# Arduino-Rework_Station.net
KiCad netlist of a schematic drawn in EAGLE
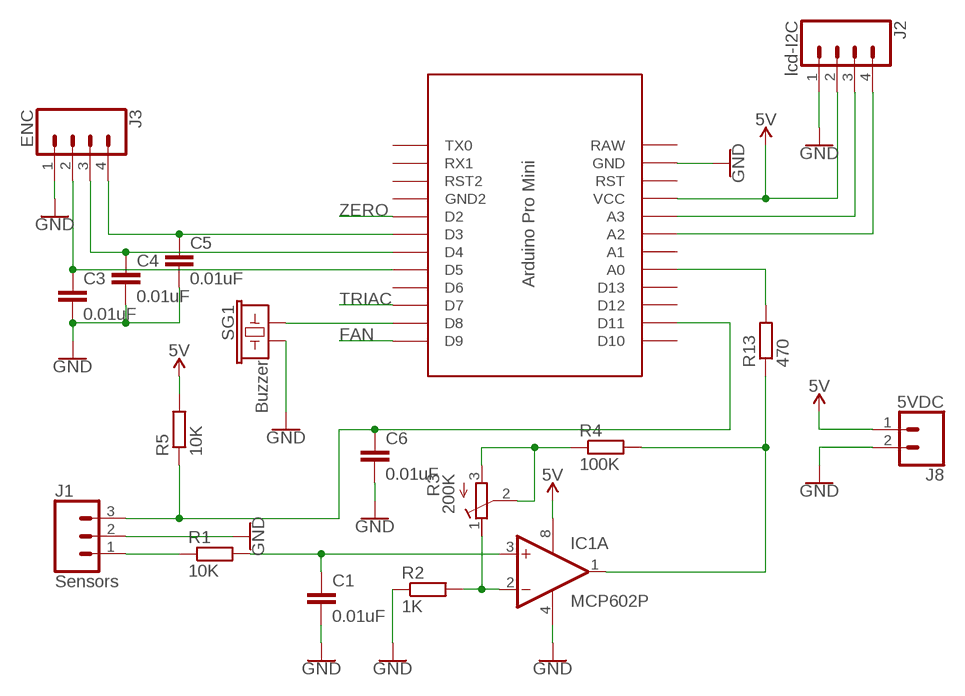
[diagram p0: schematic, sheet 1]
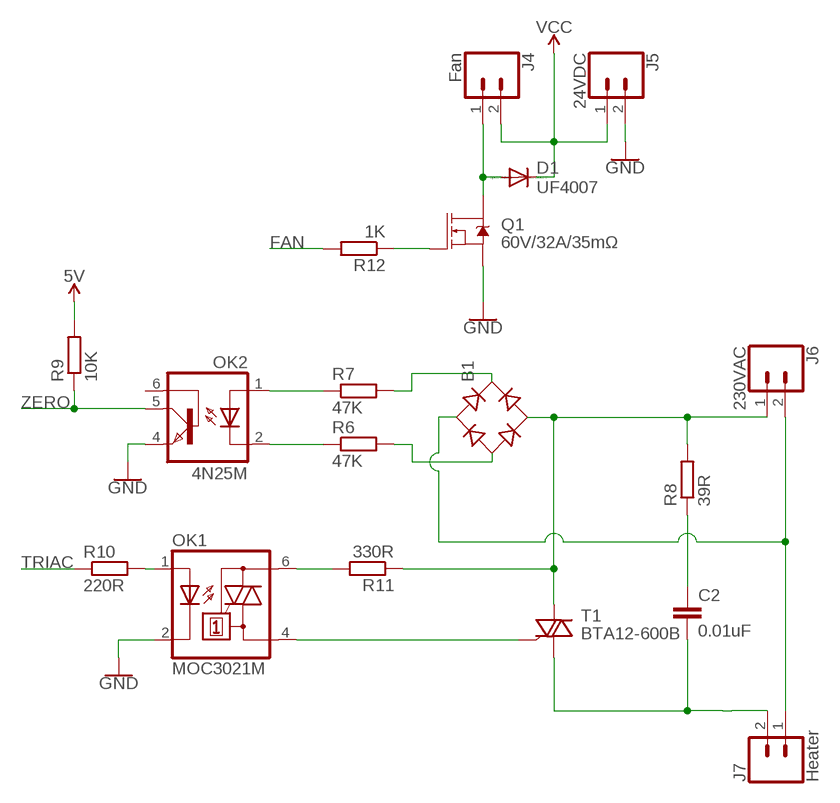
[diagram p1: schematic, sheet 2]

(export (version "E")
  (design (tool "Eeschema 10.0.6"))
  (components
    (comp (ref "C1")
      (value "0.01uF")
      (footprint "eagle-import:C025-024X044")
      (libsource (lib "eagle-import") (part "C-EU025-024X044"))
    )
    (comp (ref "C3")
      (value "0.01uF")
      (footprint "eagle-import:C025-024X044")
      (libsource (lib "eagle-import") (part "C-EU025-024X044"))
    )
    (comp (ref "C4")
      (value "0.01uF")
      (footprint "eagle-import:C025-024X044")
      (libsource (lib "eagle-import") (part "C-EU025-024X044"))
    )
    (comp (ref "C5")
      (value "0.01uF")
      (footprint "eagle-import:C025-024X044")
      (libsource (lib "eagle-import") (part "C-EU025-024X044"))
    )
    (comp (ref "C6")
      (value "0.01uF")
      (footprint "eagle-import:C025-024X044")
      (libsource (lib "eagle-import") (part "C-EU025-024X044"))
    )
    (comp (ref "IC1")
      (value "MCP602P")
      (footprint "eagle-import:DIL08")
      (libsource (lib "eagle-import") (part "MCP602P"))
    )
    (comp (ref "J1")
      (value "Sensors")
      (footprint "eagle-import:MOLEX-1X3")
      (libsource (lib "eagle-import") (part "CONN_03POLAR"))
    )
    (comp (ref "J2")
      (value "lcd-I2C")
      (footprint "eagle-import:MOLEX-1X4")
      (libsource (lib "eagle-import") (part "CONN_04POLAR"))
    )
    (comp (ref "J3")
      (value "ENC")
      (footprint "eagle-import:MOLEX-1X4")
      (libsource (lib "eagle-import") (part "CONN_04POLAR"))
    )
    (comp (ref "J8")
      (value "5VDC")
      (footprint "eagle-import:MOLEX-1X2")
      (libsource (lib "eagle-import") (part "CONN_02POLAR"))
    )
    (comp (ref "R1")
      (value "10K")
      (footprint "eagle-import:0207_10")
      (libsource (lib "eagle-import") (part "R-EU_0207/10"))
    )
    (comp (ref "R2")
      (value "1K")
      (footprint "eagle-import:0207_10")
      (libsource (lib "eagle-import") (part "R-EU_0207/10"))
    )
    (comp (ref "R3")
      (value "200K")
      (footprint "eagle-import:RTRIM3006P")
      (libsource (lib "eagle-import") (part "R-TRIMM3006P"))
    )
    (comp (ref "R4")
      (value "100K")
      (footprint "eagle-import:0207_10")
      (libsource (lib "eagle-import") (part "R-EU_0207/10"))
    )
    (comp (ref "R5")
      (value "10K")
      (footprint "eagle-import:0207_10")
      (libsource (lib "eagle-import") (part "R-EU_0207/10"))
    )
    (comp (ref "R13")
      (value "470")
      (footprint "eagle-import:0207_10")
      (libsource (lib "eagle-import") (part "R-EU_0207/10"))
    )
    (comp (ref "SG1")
      (value "Buzzer")
      (footprint "eagle-import:BUZZER-12MM")
      (libsource (lib "eagle-import") (part "BUZZER-PTH"))
    )
    (comp (ref "U$1")
      (value "PRO-MINI")
      (footprint "eagle-import:PRO-MINI")
      (libsource (lib "eagle-import") (part "PRO-MINI"))
    )
    (comp (ref "B1")
      (value "RB1A")
      (footprint "eagle-import:RB1A")
      (libsource (lib "eagle-import") (part "RB1A"))
    )
    (comp (ref "C2")
      (value "0.01uF")
      (footprint "eagle-import:C050-045X075")
      (libsource (lib "eagle-import") (part "C-EU050-045X075"))
    )
    (comp (ref "D1")
      (value "UF4007")
      (footprint "eagle-import:DO41-10")
      (libsource (lib "eagle-import") (part "1N4004"))
    )
    (comp (ref "J4")
      (value "Fan")
      (footprint "eagle-import:MOLEX-1X2")
      (libsource (lib "eagle-import") (part "CONN_02POLAR"))
    )
    (comp (ref "J5")
      (value "24VDC")
      (footprint "eagle-import:SCREWTERMINAL-5MM-2")
      (libsource (lib "eagle-import") (part "CONN_025MM"))
    )
    (comp (ref "J6")
      (value "230VAC")
      (footprint "eagle-import:1X02_XTRA_BIG")
      (libsource (lib "eagle-import") (part "CONN_02PTH4"))
    )
    (comp (ref "J7")
      (value "Heater")
      (footprint "eagle-import:1X02_XTRA_BIG")
      (libsource (lib "eagle-import") (part "CONN_02PTH4"))
    )
    (comp (ref "OK1")
      (value "MOC3021M")
      (footprint "eagle-import:DIL06")
      (fields (field (name "MF") "FAIRCHILD SEMICONDUCTOR") (field (name "MPN") "MOC3021-M"))
      (libsource (lib "eagle-import") (part "MOC30M21"))
    )
    (comp (ref "OK2")
      (value "4N25M")
      (footprint "eagle-import:DIL06")
      (fields (field (name "MPN") "4N25-M"))
      (libsource (lib "eagle-import") (part "4N?M25"))
    )
    (comp (ref "Q1")
      (value "60V/32A/35mΩ")
      (footprint "eagle-import:TO220V")
      (libsource (lib "eagle-import") (part "MOSFET-NCH-FQP30N06L"))
    )
    (comp (ref "R6")
      (value "47K")
      (footprint "eagle-import:0204_7")
      (libsource (lib "eagle-import") (part "R-EU_0204/7"))
    )
    (comp (ref "R7")
      (value "47K")
      (footprint "eagle-import:0204_7")
      (libsource (lib "eagle-import") (part "R-EU_0204/7"))
    )
    (comp (ref "R8")
      (value "39R")
      (footprint "eagle-import:0617_22")
      (libsource (lib "eagle-import") (part "R-EU_0617/22"))
    )
    (comp (ref "R9")
      (value "10K")
      (footprint "eagle-import:0204_7")
      (libsource (lib "eagle-import") (part "R-EU_0204/7"))
    )
    (comp (ref "R10")
      (value "220R")
      (footprint "eagle-import:0204_7")
      (libsource (lib "eagle-import") (part "R-EU_0204/7"))
    )
    (comp (ref "R11")
      (value "330R")
      (footprint "eagle-import:0204_7")
      (libsource (lib "eagle-import") (part "R-EU_0204/7"))
    )
    (comp (ref "R12")
      (value "1K")
      (footprint "eagle-import:0204_7")
      (libsource (lib "eagle-import") (part "R-EU_0204/7"))
    )
    (comp (ref "T1")
      (value "BTA12-600B")
      (footprint "eagle-import:TO220BV")
      (libsource (lib "eagle-import") (part "BT138-V"))
    )
  )
  (nets
    (net (code "1") (name "5V") (class "Default")
      (node (ref "IC1") (pin "8") (pinfunction "V+_8") (pintype "power_in"))
      (node (ref "J2") (pin "2") (pinfunction "2_2") (pintype "passive"))
      (node (ref "J8") (pin "1") (pinfunction "1_1") (pintype "passive"))
      (node (ref "R5") (pin "2") (pinfunction "2_2") (pintype "passive"))
      (node (ref "R9") (pin "2") (pinfunction "2_2") (pintype "passive"))
      (node (ref "U$1") (pin "VCC") (pinfunction "VCC_VCC") (pintype "bidirectional"))
    )
    (net (code "2") (name "FAN") (class "Default")
      (node (ref "R12") (pin "2") (pinfunction "2_2") (pintype "passive"))
      (node (ref "U$1") (pin "D9") (pinfunction "D9_D9") (pintype "bidirectional"))
    )
    (net (code "3") (name "GND") (class "Default")
      (node (ref "C1") (pin "2") (pinfunction "2_2") (pintype "passive"))
      (node (ref "C3") (pin "2") (pinfunction "2_2") (pintype "passive"))
      (node (ref "C4") (pin "2") (pinfunction "2_2") (pintype "passive"))
      (node (ref "C5") (pin "2") (pinfunction "2_2") (pintype "passive"))
      (node (ref "C6") (pin "2") (pinfunction "2_2") (pintype "passive"))
      (node (ref "IC1") (pin "4") (pinfunction "V-_4") (pintype "power_in"))
      (node (ref "J1") (pin "2") (pinfunction "2_2") (pintype "passive"))
      (node (ref "J2") (pin "1") (pinfunction "1_1") (pintype "passive"))
      (node (ref "J3") (pin "1") (pinfunction "1_1") (pintype "passive"))
      (node (ref "J5") (pin "2") (pinfunction "2_2") (pintype "passive"))
      (node (ref "J8") (pin "2") (pinfunction "2_2") (pintype "passive"))
      (node (ref "OK1") (pin "2") (pinfunction "C_2") (pintype "passive"))
      (node (ref "OK2") (pin "4") (pinfunction "EMI_4") (pintype "passive"))
      (node (ref "Q1") (pin "3") (pinfunction "S_3") (pintype "bidirectional"))
      (node (ref "R2") (pin "1") (pinfunction "1_1") (pintype "passive"))
      (node (ref "SG1") (pin "-") (pinfunction "2_-") (pintype "passive"))
      (node (ref "U$1") (pin "GND") (pinfunction "GND_GND") (pintype "input"))
    )
    (net (code "4") (name "Net-(B1-Pad+)") (class "Default")
      (node (ref "B1") (pin "+") (pinfunction "+_+") (pintype "passive"))
      (node (ref "R7") (pin "2") (pinfunction "2_2") (pintype "passive"))
    )
    (net (code "5") (name "Net-(B1-Pad-)") (class "Default")
      (node (ref "B1") (pin "-") (pinfunction "-_-") (pintype "passive"))
      (node (ref "R6") (pin "2") (pinfunction "2_2") (pintype "passive"))
    )
    (net (code "6") (name "Net-(B1-PadAC1)") (class "Default")
      (node (ref "B1") (pin "AC1") (pinfunction "AC1_AC1") (pintype "passive"))
      (node (ref "J6") (pin "2") (pinfunction "2_2") (pintype "passive"))
      (node (ref "J7") (pin "1") (pinfunction "1_1") (pintype "passive"))
    )
    (net (code "7") (name "Net-(C2-Pad1)") (class "Default")
      (node (ref "C2") (pin "1") (pinfunction "1_1") (pintype "passive"))
      (node (ref "R8") (pin "1") (pinfunction "1_1") (pintype "passive"))
    )
    (net (code "8") (name "Net-(C3-Pad1)") (class "Default")
      (node (ref "C3") (pin "1") (pinfunction "1_1") (pintype "passive"))
      (node (ref "J3") (pin "2") (pinfunction "2_2") (pintype "passive"))
      (node (ref "U$1") (pin "D5") (pinfunction "D5_D5") (pintype "bidirectional"))
    )
    (net (code "9") (name "Net-(C4-Pad1)") (class "Default")
      (node (ref "C4") (pin "1") (pinfunction "1_1") (pintype "passive"))
      (node (ref "J3") (pin "3") (pinfunction "3_3") (pintype "passive"))
      (node (ref "U$1") (pin "D4") (pinfunction "D4_D4") (pintype "bidirectional"))
    )
    (net (code "10") (name "Net-(C5-Pad1)") (class "Default")
      (node (ref "C5") (pin "1") (pinfunction "1_1") (pintype "passive"))
      (node (ref "J3") (pin "4") (pinfunction "4_4") (pintype "passive"))
      (node (ref "U$1") (pin "D3") (pinfunction "D3_D3") (pintype "bidirectional"))
    )
    (net (code "11") (name "Net-(C6-Pad1)") (class "Default")
      (node (ref "C6") (pin "1") (pinfunction "1_1") (pintype "passive"))
      (node (ref "J1") (pin "3") (pinfunction "3_3") (pintype "passive"))
      (node (ref "R5") (pin "1") (pinfunction "1_1") (pintype "passive"))
      (node (ref "U$1") (pin "D11") (pinfunction "D11_D11") (pintype "bidirectional"))
    )
    (net (code "12") (name "Net-(IC1A-+IN)") (class "Default")
      (node (ref "C1") (pin "1") (pinfunction "1_1") (pintype "passive"))
      (node (ref "IC1") (pin "3") (pinfunction "+IN_3") (pintype "input"))
      (node (ref "R1") (pin "2") (pinfunction "2_2") (pintype "passive"))
    )
    (net (code "13") (name "Net-(IC1A--IN)") (class "Default")
      (node (ref "IC1") (pin "2") (pinfunction "-IN_2") (pintype "input"))
      (node (ref "R2") (pin "2") (pinfunction "2_2") (pintype "passive"))
      (node (ref "R3") (pin "1") (pinfunction "E_1") (pintype "passive"))
    )
    (net (code "14") (name "Net-(IC1A-OUT)") (class "Default")
      (node (ref "IC1") (pin "1") (pinfunction "OUT_1") (pintype "output"))
      (node (ref "R13") (pin "1") (pinfunction "1_1") (pintype "passive"))
      (node (ref "R4") (pin "2") (pinfunction "2_2") (pintype "passive"))
    )
    (net (code "15") (name "Net-(J1-Pad1)") (class "Default")
      (node (ref "J1") (pin "1") (pinfunction "1_1") (pintype "passive"))
      (node (ref "R1") (pin "1") (pinfunction "1_1") (pintype "passive"))
    )
    (net (code "16") (name "Net-(J2-Pad3)") (class "Default")
      (node (ref "J2") (pin "3") (pinfunction "3_3") (pintype "passive"))
      (node (ref "U$1") (pin "A3") (pinfunction "A3_A3") (pintype "bidirectional"))
    )
    (net (code "17") (name "Net-(J2-Pad4)") (class "Default")
      (node (ref "J2") (pin "4") (pinfunction "4_4") (pintype "passive"))
      (node (ref "U$1") (pin "A2") (pinfunction "A2_A2") (pintype "bidirectional"))
    )
    (net (code "18") (name "Net-(OK1-A)") (class "Default")
      (node (ref "OK1") (pin "1") (pinfunction "A_1") (pintype "passive"))
      (node (ref "R10") (pin "2") (pinfunction "2_2") (pintype "passive"))
    )
    (net (code "19") (name "Net-(OK1-A1)") (class "Default")
      (node (ref "OK1") (pin "4") (pinfunction "A1_4") (pintype "passive"))
      (node (ref "T1") (pin "G") (pinfunction "G_G") (pintype "passive"))
    )
    (net (code "20") (name "Net-(OK1-A2)") (class "Default")
      (node (ref "OK1") (pin "6") (pinfunction "A2_6") (pintype "passive"))
      (node (ref "R11") (pin "2") (pinfunction "2_2") (pintype "passive"))
    )
    (net (code "21") (name "Net-(OK2-A)") (class "Default")
      (node (ref "OK2") (pin "1") (pinfunction "A_1") (pintype "passive"))
      (node (ref "R7") (pin "1") (pinfunction "1_1") (pintype "passive"))
    )
    (net (code "22") (name "Net-(OK2-C)") (class "Default")
      (node (ref "OK2") (pin "2") (pinfunction "C_2") (pintype "passive"))
      (node (ref "R6") (pin "1") (pinfunction "1_1") (pintype "passive"))
    )
    (net (code "23") (name "Net-(Q1-D)") (class "Default")
      (node (ref "D1") (pin "A") (pinfunction "A_A") (pintype "passive"))
      (node (ref "J4") (pin "1") (pinfunction "1_1") (pintype "passive"))
      (node (ref "Q1") (pin "2") (pinfunction "D_2") (pintype "bidirectional"))
    )
    (net (code "24") (name "Net-(Q1-G)") (class "Default")
      (node (ref "Q1") (pin "1") (pinfunction "G_1") (pintype "bidirectional"))
      (node (ref "R12") (pin "1") (pinfunction "1_1") (pintype "passive"))
    )
    (net (code "25") (name "Net-(R3-A)") (class "Default")
      (node (ref "R3") (pin "2") (pinfunction "S_2") (pintype "passive"))
      (node (ref "R3") (pin "3") (pinfunction "A_3") (pintype "passive"))
      (node (ref "R4") (pin "1") (pinfunction "1_1") (pintype "passive"))
    )
    (net (code "26") (name "Net-(R13-Pad2)") (class "Default")
      (node (ref "R13") (pin "2") (pinfunction "2_2") (pintype "passive"))
      (node (ref "U$1") (pin "A0") (pinfunction "A0_A0") (pintype "bidirectional"))
    )
    (net (code "27") (name "Net-(SG1-1)") (class "Default")
      (node (ref "SG1") (pin "+") (pinfunction "1_+") (pintype "passive"))
      (node (ref "U$1") (pin "D8") (pinfunction "D8_D8") (pintype "bidirectional"))
    )
    (net (code "28") (name "Net-(T1-A1)") (class "Default")
      (node (ref "C2") (pin "2") (pinfunction "2_2") (pintype "passive"))
      (node (ref "J7") (pin "2") (pinfunction "2_2") (pintype "passive"))
      (node (ref "T1") (pin "T1") (pinfunction "A1_T1") (pintype "passive"))
    )
    (net (code "29") (name "Net-(T1-A2)") (class "Default")
      (node (ref "B1") (pin "AC2") (pinfunction "AC2_AC2") (pintype "passive"))
      (node (ref "J6") (pin "1") (pinfunction "1_1") (pintype "passive"))
      (node (ref "R11") (pin "1") (pinfunction "1_1") (pintype "passive"))
      (node (ref "R8") (pin "2") (pinfunction "2_2") (pintype "passive"))
      (node (ref "T1") (pin "T2") (pinfunction "A2_T2") (pintype "passive"))
    )
    (net (code "30") (name "RAW") (class "Default")
      (node (ref "U$1") (pin "RAW") (pinfunction "RAW_RAW") (pintype "power_in"))
    )
    (net (code "31") (name "TRIAC") (class "Default")
      (node (ref "R10") (pin "1") (pinfunction "1_1") (pintype "passive"))
      (node (ref "U$1") (pin "D7") (pinfunction "D7_D7") (pintype "bidirectional"))
    )
    (net (code "32") (name "VCC") (class "Default")
      (node (ref "D1") (pin "C") (pinfunction "C_C") (pintype "passive"))
      (node (ref "J4") (pin "2") (pinfunction "2_2") (pintype "passive"))
      (node (ref "J5") (pin "1") (pinfunction "1_1") (pintype "passive"))
    )
    (net (code "33") (name "ZERO") (class "Default")
      (node (ref "OK2") (pin "5") (pinfunction "COL_5") (pintype "passive"))
      (node (ref "R9") (pin "1") (pinfunction "1_1") (pintype "passive"))
      (node (ref "U$1") (pin "D2") (pinfunction "D2_D2") (pintype "bidirectional"))
    )
    (net (code "34") (name "unconnected-(OK2-BAS-Pad6)") (class "Default")
      (node (ref "OK2") (pin "6") (pinfunction "BAS_6") (pintype "passive"))
    )
    (net (code "35") (name "unconnected-(U$1-GND2-PadGND1)") (class "Default")
      (node (ref "U$1") (pin "GND1") (pinfunction "GND2_GND1") (pintype "bidirectional"))
    )
    (net (code "36") (name "unconnected-(U$1-PadA1)") (class "Default")
      (node (ref "U$1") (pin "A1") (pinfunction "A1_A1") (pintype "bidirectional"))
    )
    (net (code "37") (name "unconnected-(U$1-PadD6)") (class "Default")
      (node (ref "U$1") (pin "D6") (pinfunction "D6_D6") (pintype "bidirectional"))
    )
    (net (code "38") (name "unconnected-(U$1-PadD10)") (class "Default")
      (node (ref "U$1") (pin "D10") (pinfunction "D10_D10") (pintype "bidirectional"))
    )
    (net (code "39") (name "unconnected-(U$1-PadD12)") (class "Default")
      (node (ref "U$1") (pin "D12") (pinfunction "D12_D12") (pintype "bidirectional"))
    )
    (net (code "40") (name "unconnected-(U$1-PadD13)") (class "Default")
      (node (ref "U$1") (pin "D13") (pinfunction "D13_D13") (pintype "bidirectional"))
    )
    (net (code "41") (name "unconnected-(U$1-PadRST)") (class "Default")
      (node (ref "U$1") (pin "RST") (pinfunction "RST_RST") (pintype "bidirectional"))
    )
    (net (code "42") (name "unconnected-(U$1-PadRX1)") (class "Default")
      (node (ref "U$1") (pin "RX1") (pinfunction "RX1_RX1") (pintype "bidirectional"))
    )
    (net (code "43") (name "unconnected-(U$1-PadTX0)") (class "Default")
      (node (ref "U$1") (pin "TX0") (pinfunction "TX0_TX0") (pintype "bidirectional"))
    )
    (net (code "44") (name "unconnected-(U$1-RST2-PadRST1)") (class "Default")
      (node (ref "U$1") (pin "RST1") (pinfunction "RST2_RST1") (pintype "bidirectional"))
    )
  )
)
